# esp-module-cu.net
KiCad netlist of a schematic drawn in EAGLE
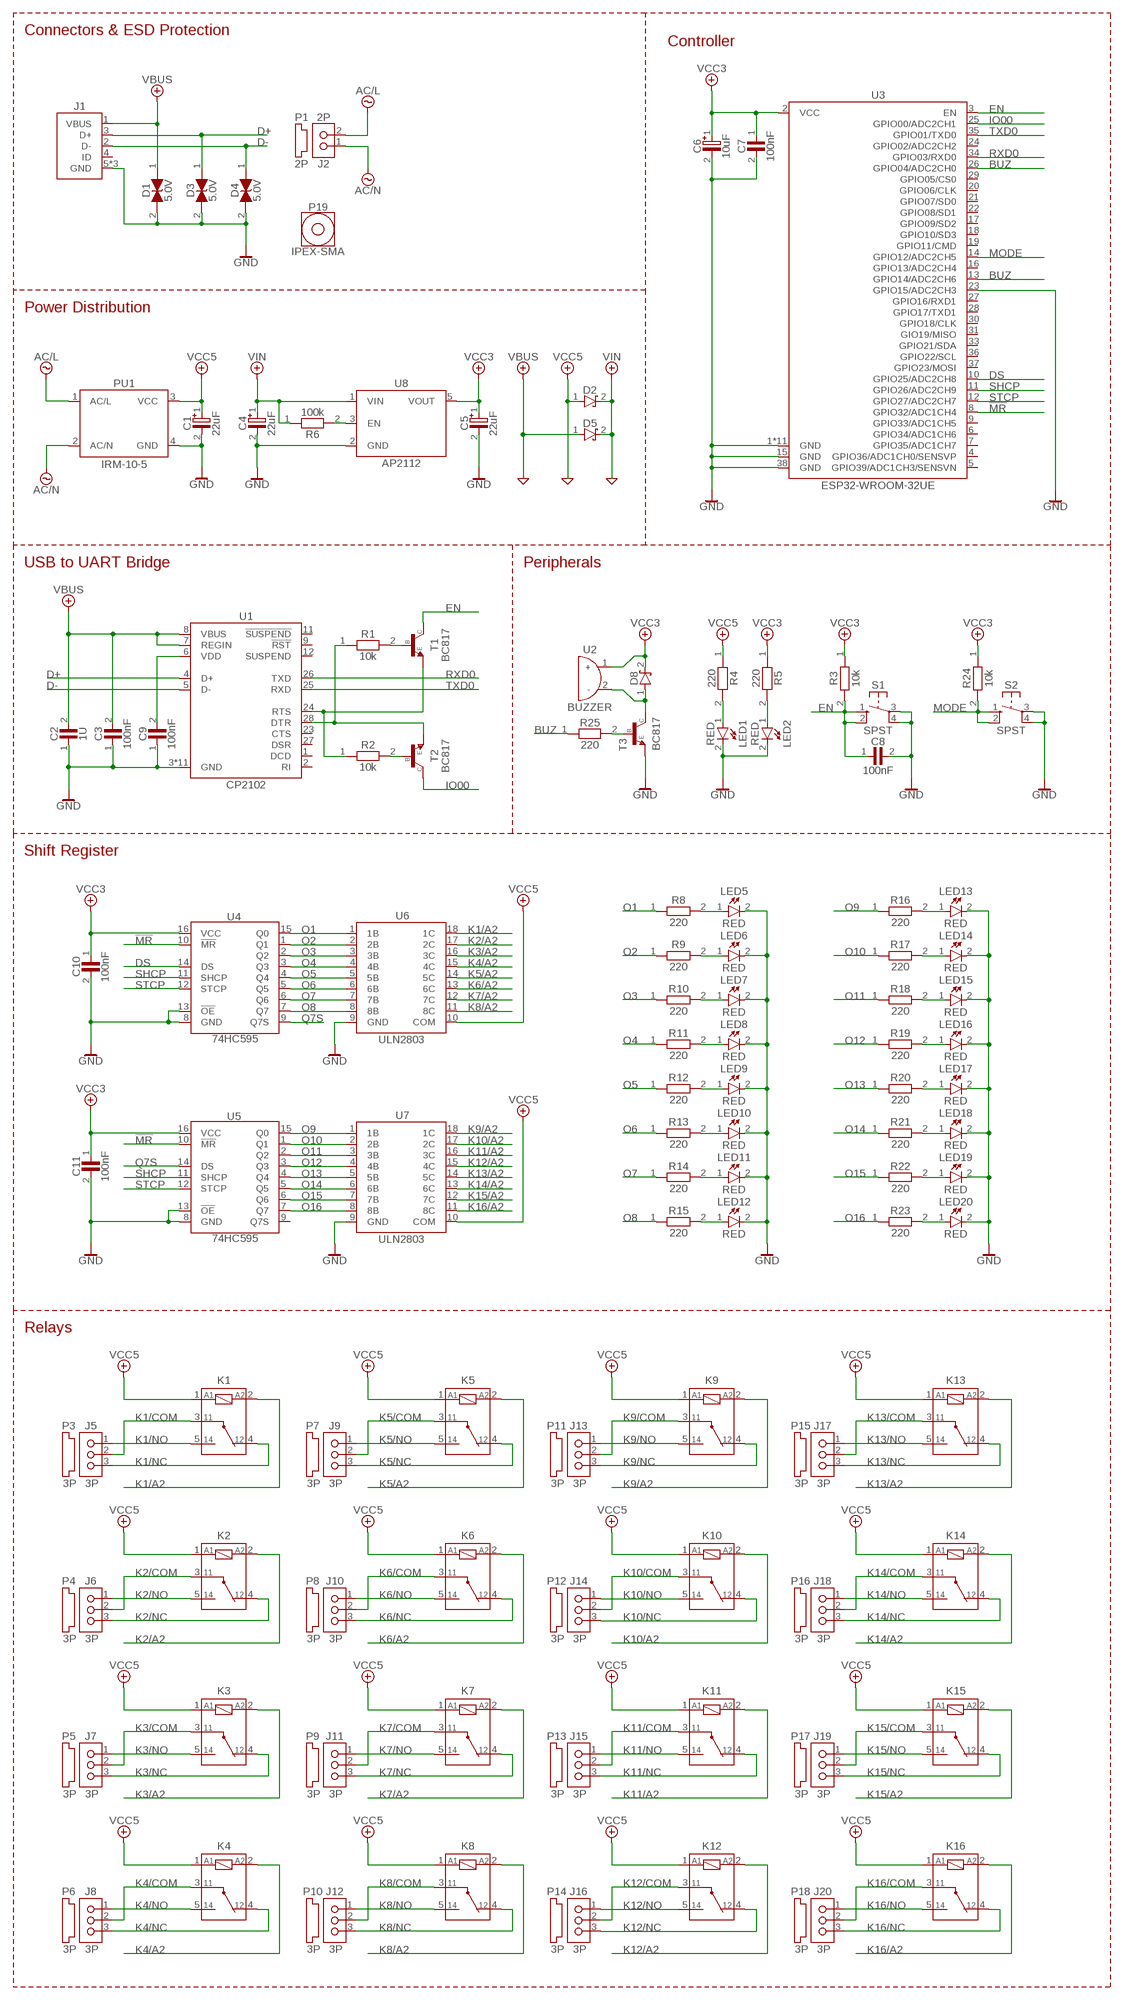
[diagram p0: schematic, sheet 1]

(export (version "E")
  (design (tool "Eeschema 10.0.6"))
  (components
    (comp (ref "C1")
      (value "22uF")
      (footprint "eagle-import:I1206-M3216-D")
      (fields
        (field (name "MF") "Kyocera AVX")
        (field (name "MPN") "TAJA226K010RNJ")
        (field (name "VOLTAGE") "10V")
      )
      (libsource (lib "eagle-import") (part "CAPACITOR-TANTALUM-I1206-M3216-22U"))
    )
    (comp (ref "C2")
      (value "1U")
      (footprint "eagle-import:I0805-M2012-C")
      (fields
        (field (name "MF") " FH (Guangdong Fenghua Advanced Tech)")
        (field (name "MPN") "0805B105K500NT")
        (field (name "TOLERANCE") "10%")
      )
      (libsource (lib "eagle-import") (part "CAPACITOR-CERAMIC-I0805-M2012-1U"))
    )
    (comp (ref "C3")
      (value "100nF")
      (footprint "eagle-import:I0805-M2012-C")
      (fields
        (field (name "MF") "FH (Guangdong Fenghua Advanced Tech)")
        (field (name "MPN") "0805B104K500NT")
        (field (name "TOLERANCE") "10%")
      )
      (libsource (lib "eagle-import") (part "CAPACITOR-CERAMIC-I0805-M2012-100N"))
    )
    (comp (ref "C4")
      (value "22uF")
      (footprint "eagle-import:I1206-M3216-D")
      (fields
        (field (name "MF") "Kyocera AVX")
        (field (name "MPN") "TAJA226K010RNJ")
        (field (name "VOLTAGE") "10V")
      )
      (libsource (lib "eagle-import") (part "CAPACITOR-TANTALUM-I1206-M3216-22U"))
    )
    (comp (ref "C5")
      (value "22uF")
      (footprint "eagle-import:I1206-M3216-D")
      (fields
        (field (name "MF") "Kyocera AVX")
        (field (name "MPN") "TAJA226K010RNJ")
        (field (name "VOLTAGE") "10V")
      )
      (libsource (lib "eagle-import") (part "CAPACITOR-TANTALUM-I1206-M3216-22U"))
    )
    (comp (ref "C6")
      (value "10uF")
      (footprint "eagle-import:I1206-M3216-D")
      (fields
        (field (name "MF") "Kyocera AVX")
        (field (name "MPN") "TAJA106K016RNJ")
        (field (name "VOLTAGE") "16V")
      )
      (libsource (lib "eagle-import") (part "CAPACITOR-TANTALUM-I1206-M3216-10U"))
    )
    (comp (ref "C7")
      (value "100nF")
      (footprint "eagle-import:I0805-M2012-C")
      (fields
        (field (name "MF") "FH (Guangdong Fenghua Advanced Tech)")
        (field (name "MPN") "0805B104K500NT")
        (field (name "TOLERANCE") "10%")
      )
      (libsource (lib "eagle-import") (part "CAPACITOR-CERAMIC-I0805-M2012-100N"))
    )
    (comp (ref "C8")
      (value "100nF")
      (footprint "eagle-import:I0805-M2012-C")
      (fields
        (field (name "MF") "FH (Guangdong Fenghua Advanced Tech)")
        (field (name "MPN") "0805B104K500NT")
        (field (name "TOLERANCE") "10%")
      )
      (libsource (lib "eagle-import") (part "CAPACITOR-CERAMIC-I0805-M2012-100N"))
    )
    (comp (ref "C9")
      (value "100nF")
      (footprint "eagle-import:I0805-M2012-C")
      (fields
        (field (name "MF") "FH (Guangdong Fenghua Advanced Tech)")
        (field (name "MPN") "0805B104K500NT")
        (field (name "TOLERANCE") "10%")
      )
      (libsource (lib "eagle-import") (part "CAPACITOR-CERAMIC-I0805-M2012-100N"))
    )
    (comp (ref "C10")
      (value "100nF")
      (footprint "eagle-import:I0805-M2012-C")
      (fields
        (field (name "MF") "FH (Guangdong Fenghua Advanced Tech)")
        (field (name "MPN") "0805B104K500NT")
        (field (name "TOLERANCE") "10%")
      )
      (libsource (lib "eagle-import") (part "CAPACITOR-CERAMIC-I0805-M2012-100N"))
    )
    (comp (ref "C11")
      (value "100nF")
      (footprint "eagle-import:I0805-M2012-C")
      (fields
        (field (name "MF") "FH (Guangdong Fenghua Advanced Tech)")
        (field (name "MPN") "0805B104K500NT")
        (field (name "TOLERANCE") "10%")
      )
      (libsource (lib "eagle-import") (part "CAPACITOR-CERAMIC-I0805-M2012-100N"))
    )
    (comp (ref "D1")
      (value "5.0V")
      (footprint "eagle-import:SOD-523")
      (fields (field (name "MF") " LRC") (field (name "MPN") "LESD5D5.0CT1G"))
      (libsource (lib "eagle-import") (part "ZENER-BI-SOD-523-5.0V"))
    )
    (comp (ref "D2")
      (value "30V")
      (footprint "eagle-import:SOD-323")
      (fields (field (name "MF") "Diodes Incorporated") (field (name "MPN") "BAT760-7"))
      (libsource (lib "eagle-import") (part "SCHOTTKY-SOD-323-30V"))
    )
    (comp (ref "D3")
      (value "5.0V")
      (footprint "eagle-import:SOD-523")
      (fields (field (name "MF") " LRC") (field (name "MPN") "LESD5D5.0CT1G"))
      (libsource (lib "eagle-import") (part "ZENER-BI-SOD-523-5.0V"))
    )
    (comp (ref "D4")
      (value "5.0V")
      (footprint "eagle-import:SOD-523")
      (fields (field (name "MF") " LRC") (field (name "MPN") "LESD5D5.0CT1G"))
      (libsource (lib "eagle-import") (part "ZENER-BI-SOD-523-5.0V"))
    )
    (comp (ref "D5")
      (value "30V")
      (footprint "eagle-import:SOD-323")
      (fields (field (name "MF") "Diodes Incorporated") (field (name "MPN") "BAT760-7"))
      (libsource (lib "eagle-import") (part "SCHOTTKY-SOD-323-30V"))
    )
    (comp (ref "D8")
      (value "30V")
      (footprint "eagle-import:SOD-323")
      (fields (field (name "MF") "Diodes Incorporated") (field (name "MPN") "BAT760-7"))
      (libsource (lib "eagle-import") (part "SCHOTTKY-SOD-323-30V"))
    )
    (comp (ref "J1")
      (value "USB-A-MICRO-TOP")
      (footprint "eagle-import:USB-A-MICRO-TOP")
      (fields (field (name "MF") "XKB Connectivity") (field (name "MPN") "U255-051N-4BH70-FS"))
      (libsource (lib "eagle-import") (part "USB-A-MICRO-TOP"))
    )
    (comp (ref "J2")
      (value "2P")
      (footprint "eagle-import:KF2EDGV-5.08-2P")
      (fields (field (name "MF") "Cixi Kefa Elec") (field (name "MPN") "KF2EDGV-5.08-2P"))
      (libsource (lib "eagle-import") (part "HEADER-02P-1R-KF2EDGV-5.08-2P"))
    )
    (comp (ref "J5")
      (value "3P")
      (footprint "eagle-import:KF2EDGV-5.08-3P")
      (fields (field (name "MF") " Cixi Kefa Elec") (field (name "MPN") " KF2EDGV-5.08-3P"))
      (libsource (lib "eagle-import") (part "HEADER-03P-1R-KF2EDGV-5.08-3P"))
    )
    (comp (ref "J6")
      (value "3P")
      (footprint "eagle-import:KF2EDGV-5.08-3P")
      (fields (field (name "MF") " Cixi Kefa Elec") (field (name "MPN") " KF2EDGV-5.08-3P"))
      (libsource (lib "eagle-import") (part "HEADER-03P-1R-KF2EDGV-5.08-3P"))
    )
    (comp (ref "J7")
      (value "3P")
      (footprint "eagle-import:KF2EDGV-5.08-3P")
      (fields (field (name "MF") " Cixi Kefa Elec") (field (name "MPN") " KF2EDGV-5.08-3P"))
      (libsource (lib "eagle-import") (part "HEADER-03P-1R-KF2EDGV-5.08-3P"))
    )
    (comp (ref "J8")
      (value "3P")
      (footprint "eagle-import:KF2EDGV-5.08-3P")
      (fields (field (name "MF") " Cixi Kefa Elec") (field (name "MPN") " KF2EDGV-5.08-3P"))
      (libsource (lib "eagle-import") (part "HEADER-03P-1R-KF2EDGV-5.08-3P"))
    )
    (comp (ref "J9")
      (value "3P")
      (footprint "eagle-import:KF2EDGV-5.08-3P")
      (fields (field (name "MF") " Cixi Kefa Elec") (field (name "MPN") " KF2EDGV-5.08-3P"))
      (libsource (lib "eagle-import") (part "HEADER-03P-1R-KF2EDGV-5.08-3P"))
    )
    (comp (ref "J10")
      (value "3P")
      (footprint "eagle-import:KF2EDGV-5.08-3P")
      (fields (field (name "MF") " Cixi Kefa Elec") (field (name "MPN") " KF2EDGV-5.08-3P"))
      (libsource (lib "eagle-import") (part "HEADER-03P-1R-KF2EDGV-5.08-3P"))
    )
    (comp (ref "J11")
      (value "3P")
      (footprint "eagle-import:KF2EDGV-5.08-3P")
      (fields (field (name "MF") " Cixi Kefa Elec") (field (name "MPN") " KF2EDGV-5.08-3P"))
      (libsource (lib "eagle-import") (part "HEADER-03P-1R-KF2EDGV-5.08-3P"))
    )
    (comp (ref "J12")
      (value "3P")
      (footprint "eagle-import:KF2EDGV-5.08-3P")
      (fields (field (name "MF") " Cixi Kefa Elec") (field (name "MPN") " KF2EDGV-5.08-3P"))
      (libsource (lib "eagle-import") (part "HEADER-03P-1R-KF2EDGV-5.08-3P"))
    )
    (comp (ref "J13")
      (value "3P")
      (footprint "eagle-import:KF2EDGV-5.08-3P")
      (fields (field (name "MF") " Cixi Kefa Elec") (field (name "MPN") " KF2EDGV-5.08-3P"))
      (libsource (lib "eagle-import") (part "HEADER-03P-1R-KF2EDGV-5.08-3P"))
    )
    (comp (ref "J14")
      (value "3P")
      (footprint "eagle-import:KF2EDGV-5.08-3P")
      (fields (field (name "MF") " Cixi Kefa Elec") (field (name "MPN") " KF2EDGV-5.08-3P"))
      (libsource (lib "eagle-import") (part "HEADER-03P-1R-KF2EDGV-5.08-3P"))
    )
    (comp (ref "J15")
      (value "3P")
      (footprint "eagle-import:KF2EDGV-5.08-3P")
      (fields (field (name "MF") " Cixi Kefa Elec") (field (name "MPN") " KF2EDGV-5.08-3P"))
      (libsource (lib "eagle-import") (part "HEADER-03P-1R-KF2EDGV-5.08-3P"))
    )
    (comp (ref "J16")
      (value "3P")
      (footprint "eagle-import:KF2EDGV-5.08-3P")
      (fields (field (name "MF") " Cixi Kefa Elec") (field (name "MPN") " KF2EDGV-5.08-3P"))
      (libsource (lib "eagle-import") (part "HEADER-03P-1R-KF2EDGV-5.08-3P"))
    )
    (comp (ref "J17")
      (value "3P")
      (footprint "eagle-import:KF2EDGV-5.08-3P")
      (fields (field (name "MF") " Cixi Kefa Elec") (field (name "MPN") " KF2EDGV-5.08-3P"))
      (libsource (lib "eagle-import") (part "HEADER-03P-1R-KF2EDGV-5.08-3P"))
    )
    (comp (ref "J18")
      (value "3P")
      (footprint "eagle-import:KF2EDGV-5.08-3P")
      (fields (field (name "MF") " Cixi Kefa Elec") (field (name "MPN") " KF2EDGV-5.08-3P"))
      (libsource (lib "eagle-import") (part "HEADER-03P-1R-KF2EDGV-5.08-3P"))
    )
    (comp (ref "J19")
      (value "3P")
      (footprint "eagle-import:KF2EDGV-5.08-3P")
      (fields (field (name "MF") " Cixi Kefa Elec") (field (name "MPN") " KF2EDGV-5.08-3P"))
      (libsource (lib "eagle-import") (part "HEADER-03P-1R-KF2EDGV-5.08-3P"))
    )
    (comp (ref "J20")
      (value "3P")
      (footprint "eagle-import:KF2EDGV-5.08-3P")
      (fields (field (name "MF") " Cixi Kefa Elec") (field (name "MPN") " KF2EDGV-5.08-3P"))
      (libsource (lib "eagle-import") (part "HEADER-03P-1R-KF2EDGV-5.08-3P"))
    )
    (comp (ref "K1")
      (value "5V")
      (footprint "eagle-import:SRD")
      (fields (field (name "MF") "Ningbo Songle Relay") (field (name "MPN") " SRD-05VDC-SL-C"))
      (libsource (lib "eagle-import") (part "RELAY-SPDT-SRD-5V"))
    )
    (comp (ref "K2")
      (value "5V")
      (footprint "eagle-import:SRD")
      (fields (field (name "MF") "Ningbo Songle Relay") (field (name "MPN") " SRD-05VDC-SL-C"))
      (libsource (lib "eagle-import") (part "RELAY-SPDT-SRD-5V"))
    )
    (comp (ref "K3")
      (value "5V")
      (footprint "eagle-import:SRD")
      (fields (field (name "MF") "Ningbo Songle Relay") (field (name "MPN") " SRD-05VDC-SL-C"))
      (libsource (lib "eagle-import") (part "RELAY-SPDT-SRD-5V"))
    )
    (comp (ref "K4")
      (value "5V")
      (footprint "eagle-import:SRD")
      (fields (field (name "MF") "Ningbo Songle Relay") (field (name "MPN") " SRD-05VDC-SL-C"))
      (libsource (lib "eagle-import") (part "RELAY-SPDT-SRD-5V"))
    )
    (comp (ref "K5")
      (value "5V")
      (footprint "eagle-import:SRD")
      (fields (field (name "MF") "Ningbo Songle Relay") (field (name "MPN") " SRD-05VDC-SL-C"))
      (libsource (lib "eagle-import") (part "RELAY-SPDT-SRD-5V"))
    )
    (comp (ref "K6")
      (value "5V")
      (footprint "eagle-import:SRD")
      (fields (field (name "MF") "Ningbo Songle Relay") (field (name "MPN") " SRD-05VDC-SL-C"))
      (libsource (lib "eagle-import") (part "RELAY-SPDT-SRD-5V"))
    )
    (comp (ref "K7")
      (value "5V")
      (footprint "eagle-import:SRD")
      (fields (field (name "MF") "Ningbo Songle Relay") (field (name "MPN") " SRD-05VDC-SL-C"))
      (libsource (lib "eagle-import") (part "RELAY-SPDT-SRD-5V"))
    )
    (comp (ref "K8")
      (value "5V")
      (footprint "eagle-import:SRD")
      (fields (field (name "MF") "Ningbo Songle Relay") (field (name "MPN") " SRD-05VDC-SL-C"))
      (libsource (lib "eagle-import") (part "RELAY-SPDT-SRD-5V"))
    )
    (comp (ref "K9")
      (value "5V")
      (footprint "eagle-import:SRD")
      (fields (field (name "MF") "Ningbo Songle Relay") (field (name "MPN") " SRD-05VDC-SL-C"))
      (libsource (lib "eagle-import") (part "RELAY-SPDT-SRD-5V"))
    )
    (comp (ref "K10")
      (value "5V")
      (footprint "eagle-import:SRD")
      (fields (field (name "MF") "Ningbo Songle Relay") (field (name "MPN") " SRD-05VDC-SL-C"))
      (libsource (lib "eagle-import") (part "RELAY-SPDT-SRD-5V"))
    )
    (comp (ref "K11")
      (value "5V")
      (footprint "eagle-import:SRD")
      (fields (field (name "MF") "Ningbo Songle Relay") (field (name "MPN") " SRD-05VDC-SL-C"))
      (libsource (lib "eagle-import") (part "RELAY-SPDT-SRD-5V"))
    )
    (comp (ref "K12")
      (value "5V")
      (footprint "eagle-import:SRD")
      (fields (field (name "MF") "Ningbo Songle Relay") (field (name "MPN") " SRD-05VDC-SL-C"))
      (libsource (lib "eagle-import") (part "RELAY-SPDT-SRD-5V"))
    )
    (comp (ref "K13")
      (value "5V")
      (footprint "eagle-import:SRD")
      (fields (field (name "MF") "Ningbo Songle Relay") (field (name "MPN") " SRD-05VDC-SL-C"))
      (libsource (lib "eagle-import") (part "RELAY-SPDT-SRD-5V"))
    )
    (comp (ref "K14")
      (value "5V")
      (footprint "eagle-import:SRD")
      (fields (field (name "MF") "Ningbo Songle Relay") (field (name "MPN") " SRD-05VDC-SL-C"))
      (libsource (lib "eagle-import") (part "RELAY-SPDT-SRD-5V"))
    )
    (comp (ref "K15")
      (value "5V")
      (footprint "eagle-import:SRD")
      (fields (field (name "MF") "Ningbo Songle Relay") (field (name "MPN") " SRD-05VDC-SL-C"))
      (libsource (lib "eagle-import") (part "RELAY-SPDT-SRD-5V"))
    )
    (comp (ref "K16")
      (value "5V")
      (footprint "eagle-import:SRD")
      (fields (field (name "MF") "Ningbo Songle Relay") (field (name "MPN") " SRD-05VDC-SL-C"))
      (libsource (lib "eagle-import") (part "RELAY-SPDT-SRD-5V"))
    )
    (comp (ref "LED1")
      (value "RED")
      (footprint "eagle-import:I0805-M2012-D")
      (fields (field (name "MF") "Foshan NationStar Optoelectronics") (field (name "MPN") "FC-2012HRK-620D"))
      (libsource (lib "eagle-import") (part "LED-I0805-M2012-RED"))
    )
    (comp (ref "LED2")
      (value "RED")
      (footprint "eagle-import:I0805-M2012-D")
      (fields (field (name "MF") "Foshan NationStar Optoelectronics") (field (name "MPN") "FC-2012HRK-620D"))
      (libsource (lib "eagle-import") (part "LED-I0805-M2012-RED"))
    )
    (comp (ref "LED5")
      (value "RED")
      (footprint "eagle-import:I0805-M2012-D")
      (fields (field (name "MF") "Foshan NationStar Optoelectronics") (field (name "MPN") "FC-2012HRK-620D"))
      (libsource (lib "eagle-import") (part "LED-I0805-M2012-RED"))
    )
    (comp (ref "LED6")
      (value "RED")
      (footprint "eagle-import:I0805-M2012-D")
      (fields (field (name "MF") "Foshan NationStar Optoelectronics") (field (name "MPN") "FC-2012HRK-620D"))
      (libsource (lib "eagle-import") (part "LED-I0805-M2012-RED"))
    )
    (comp (ref "LED7")
      (value "RED")
      (footprint "eagle-import:I0805-M2012-D")
      (fields (field (name "MF") "Foshan NationStar Optoelectronics") (field (name "MPN") "FC-2012HRK-620D"))
      (libsource (lib "eagle-import") (part "LED-I0805-M2012-RED"))
    )
    (comp (ref "LED8")
      (value "RED")
      (footprint "eagle-import:I0805-M2012-D")
      (fields (field (name "MF") "Foshan NationStar Optoelectronics") (field (name "MPN") "FC-2012HRK-620D"))
      (libsource (lib "eagle-import") (part "LED-I0805-M2012-RED"))
    )
    (comp (ref "LED9")
      (value "RED")
      (footprint "eagle-import:I0805-M2012-D")
      (fields (field (name "MF") "Foshan NationStar Optoelectronics") (field (name "MPN") "FC-2012HRK-620D"))
      (libsource (lib "eagle-import") (part "LED-I0805-M2012-RED"))
    )
    (comp (ref "LED10")
      (value "RED")
      (footprint "eagle-import:I0805-M2012-D")
      (fields (field (name "MF") "Foshan NationStar Optoelectronics") (field (name "MPN") "FC-2012HRK-620D"))
      (libsource (lib "eagle-import") (part "LED-I0805-M2012-RED"))
    )
    (comp (ref "LED11")
      (value "RED")
      (footprint "eagle-import:I0805-M2012-D")
      (fields (field (name "MF") "Foshan NationStar Optoelectronics") (field (name "MPN") "FC-2012HRK-620D"))
      (libsource (lib "eagle-import") (part "LED-I0805-M2012-RED"))
    )
    (comp (ref "LED12")
      (value "RED")
      (footprint "eagle-import:I0805-M2012-D")
      (fields (field (name "MF") "Foshan NationStar Optoelectronics") (field (name "MPN") "FC-2012HRK-620D"))
      (libsource (lib "eagle-import") (part "LED-I0805-M2012-RED"))
    )
    (comp (ref "LED13")
      (value "RED")
      (footprint "eagle-import:I0805-M2012-D")
      (fields (field (name "MF") "Foshan NationStar Optoelectronics") (field (name "MPN") "FC-2012HRK-620D"))
      (libsource (lib "eagle-import") (part "LED-I0805-M2012-RED"))
    )
    (comp (ref "LED14")
      (value "RED")
      (footprint "eagle-import:I0805-M2012-D")
      (fields (field (name "MF") "Foshan NationStar Optoelectronics") (field (name "MPN") "FC-2012HRK-620D"))
      (libsource (lib "eagle-import") (part "LED-I0805-M2012-RED"))
    )
    (comp (ref "LED15")
      (value "RED")
      (footprint "eagle-import:I0805-M2012-D")
      (fields (field (name "MF") "Foshan NationStar Optoelectronics") (field (name "MPN") "FC-2012HRK-620D"))
      (libsource (lib "eagle-import") (part "LED-I0805-M2012-RED"))
    )
    (comp (ref "LED16")
      (value "RED")
      (footprint "eagle-import:I0805-M2012-D")
      (fields (field (name "MF") "Foshan NationStar Optoelectronics") (field (name "MPN") "FC-2012HRK-620D"))
      (libsource (lib "eagle-import") (part "LED-I0805-M2012-RED"))
    )
    (comp (ref "LED17")
      (value "RED")
      (footprint "eagle-import:I0805-M2012-D")
      (fields (field (name "MF") "Foshan NationStar Optoelectronics") (field (name "MPN") "FC-2012HRK-620D"))
      (libsource (lib "eagle-import") (part "LED-I0805-M2012-RED"))
    )
    (comp (ref "LED18")
      (value "RED")
      (footprint "eagle-import:I0805-M2012-D")
      (fields (field (name "MF") "Foshan NationStar Optoelectronics") (field (name "MPN") "FC-2012HRK-620D"))
      (libsource (lib "eagle-import") (part "LED-I0805-M2012-RED"))
    )
    (comp (ref "LED19")
      (value "RED")
      (footprint "eagle-import:I0805-M2012-D")
      (fields (field (name "MF") "Foshan NationStar Optoelectronics") (field (name "MPN") "FC-2012HRK-620D"))
      (libsource (lib "eagle-import") (part "LED-I0805-M2012-RED"))
    )
    (comp (ref "LED20")
      (value "RED")
      (footprint "eagle-import:I0805-M2012-D")
      (fields (field (name "MF") "Foshan NationStar Optoelectronics") (field (name "MPN") "FC-2012HRK-620D"))
      (libsource (lib "eagle-import") (part "LED-I0805-M2012-RED"))
    )
    (comp (ref "P1")
      (value "2P")
      (footprint "eagle-import:CONNECTOR-DEFAULT")
      (fields (field (name "MF") "Cixi Kefa Elec") (field (name "MPN") "KF2EDGK-5.08-2P"))
      (libsource (lib "eagle-import") (part "CONNECTOR-02P-1R-KF2EDGK-5.08"))
    )
    (comp (ref "P3")
      (value "3P")
      (footprint "eagle-import:CONNECTOR-DEFAULT")
      (fields (field (name "MF") "Cixi Kefa Elec") (field (name "MPN") " KF2EDGK-5.08-3P"))
      (libsource (lib "eagle-import") (part "CONNECTOR-03P-1R-KF2EDGK-5.08"))
    )
    (comp (ref "P4")
      (value "3P")
      (footprint "eagle-import:CONNECTOR-DEFAULT")
      (fields (field (name "MF") "Cixi Kefa Elec") (field (name "MPN") " KF2EDGK-5.08-3P"))
      (libsource (lib "eagle-import") (part "CONNECTOR-03P-1R-KF2EDGK-5.08"))
    )
    (comp (ref "P5")
      (value "3P")
      (footprint "eagle-import:CONNECTOR-DEFAULT")
      (fields (field (name "MF") "Cixi Kefa Elec") (field (name "MPN") " KF2EDGK-5.08-3P"))
      (libsource (lib "eagle-import") (part "CONNECTOR-03P-1R-KF2EDGK-5.08"))
    )
    (comp (ref "P6")
      (value "3P")
      (footprint "eagle-import:CONNECTOR-DEFAULT")
      (fields (field (name "MF") "Cixi Kefa Elec") (field (name "MPN") " KF2EDGK-5.08-3P"))
      (libsource (lib "eagle-import") (part "CONNECTOR-03P-1R-KF2EDGK-5.08"))
    )
    (comp (ref "P7")
      (value "3P")
      (footprint "eagle-import:CONNECTOR-DEFAULT")
      (fields (field (name "MF") "Cixi Kefa Elec") (field (name "MPN") " KF2EDGK-5.08-3P"))
      (libsource (lib "eagle-import") (part "CONNECTOR-03P-1R-KF2EDGK-5.08"))
    )
    (comp (ref "P8")
      (value "3P")
      (footprint "eagle-import:CONNECTOR-DEFAULT")
      (fields (field (name "MF") "Cixi Kefa Elec") (field (name "MPN") " KF2EDGK-5.08-3P"))
      (libsource (lib "eagle-import") (part "CONNECTOR-03P-1R-KF2EDGK-5.08"))
    )
    (comp (ref "P9")
      (value "3P")
      (footprint "eagle-import:CONNECTOR-DEFAULT")
      (fields (field (name "MF") "Cixi Kefa Elec") (field (name "MPN") " KF2EDGK-5.08-3P"))
      (libsource (lib "eagle-import") (part "CONNECTOR-03P-1R-KF2EDGK-5.08"))
    )
    (comp (ref "P10")
      (value "3P")
      (footprint "eagle-import:CONNECTOR-DEFAULT")
      (fields (field (name "MF") "Cixi Kefa Elec") (field (name "MPN") " KF2EDGK-5.08-3P"))
      (libsource (lib "eagle-import") (part "CONNECTOR-03P-1R-KF2EDGK-5.08"))
    )
    (comp (ref "P11")
      (value "3P")
      (footprint "eagle-import:CONNECTOR-DEFAULT")
      (fields (field (name "MF") "Cixi Kefa Elec") (field (name "MPN") " KF2EDGK-5.08-3P"))
      (libsource (lib "eagle-import") (part "CONNECTOR-03P-1R-KF2EDGK-5.08"))
    )
    (comp (ref "P12")
      (value "3P")
      (footprint "eagle-import:CONNECTOR-DEFAULT")
      (fields (field (name "MF") "Cixi Kefa Elec") (field (name "MPN") " KF2EDGK-5.08-3P"))
      (libsource (lib "eagle-import") (part "CONNECTOR-03P-1R-KF2EDGK-5.08"))
    )
    (comp (ref "P13")
      (value "3P")
      (footprint "eagle-import:CONNECTOR-DEFAULT")
      (fields (field (name "MF") "Cixi Kefa Elec") (field (name "MPN") " KF2EDGK-5.08-3P"))
      (libsource (lib "eagle-import") (part "CONNECTOR-03P-1R-KF2EDGK-5.08"))
    )
    (comp (ref "P14")
      (value "3P")
      (footprint "eagle-import:CONNECTOR-DEFAULT")
      (fields (field (name "MF") "Cixi Kefa Elec") (field (name "MPN") " KF2EDGK-5.08-3P"))
      (libsource (lib "eagle-import") (part "CONNECTOR-03P-1R-KF2EDGK-5.08"))
    )
    (comp (ref "P15")
      (value "3P")
      (footprint "eagle-import:CONNECTOR-DEFAULT")
      (fields (field (name "MF") "Cixi Kefa Elec") (field (name "MPN") " KF2EDGK-5.08-3P"))
      (libsource (lib "eagle-import") (part "CONNECTOR-03P-1R-KF2EDGK-5.08"))
    )
    (comp (ref "P16")
      (value "3P")
      (footprint "eagle-import:CONNECTOR-DEFAULT")
      (fields (field (name "MF") "Cixi Kefa Elec") (field (name "MPN") " KF2EDGK-5.08-3P"))
      (libsource (lib "eagle-import") (part "CONNECTOR-03P-1R-KF2EDGK-5.08"))
    )
    (comp (ref "P17")
      (value "3P")
      (footprint "eagle-import:CONNECTOR-DEFAULT")
      (fields (field (name "MF") "Cixi Kefa Elec") (field (name "MPN") " KF2EDGK-5.08-3P"))
      (libsource (lib "eagle-import") (part "CONNECTOR-03P-1R-KF2EDGK-5.08"))
    )
    (comp (ref "P18")
      (value "3P")
      (footprint "eagle-import:CONNECTOR-DEFAULT")
      (fields (field (name "MF") "Cixi Kefa Elec") (field (name "MPN") " KF2EDGK-5.08-3P"))
      (libsource (lib "eagle-import") (part "CONNECTOR-03P-1R-KF2EDGK-5.08"))
    )
    (comp (ref "P19")
      (value "IPEX-SMA")
      (footprint "eagle-import:SMA")
      (fields (field (name "MF") "HJ-IPEX1-SMA-RG1.13-35mm") (field (name "MPN") "HJ Tech"))
      (libsource (lib "eagle-import") (part "IPEX-SMA"))
    )
    (comp (ref "PU1")
      (value "IRM-10-5")
      (footprint "eagle-import:IRM-10")
      (fields (field (name "MF") "Mean Well"))
      (libsource (lib "eagle-import") (part "POWER-SUPPLY-IRM-10-5V"))
    )
    (comp (ref "R1")
      (value "10k")
      (footprint "eagle-import:I0805-M2012-R")
      (fields (field (name "MF") " UNI-ROYAL(Uniroyal Elec)") (field (name "MPN") "0805W8F1002T5E"))
      (libsource (lib "eagle-import") (part "RESISTOR-I0805-M2012-10K"))
    )
    (comp (ref "R2")
      (value "10k")
      (footprint "eagle-import:I0805-M2012-R")
      (fields (field (name "MF") " UNI-ROYAL(Uniroyal Elec)") (field (name "MPN") "0805W8F1002T5E"))
      (libsource (lib "eagle-import") (part "RESISTOR-I0805-M2012-10K"))
    )
    (comp (ref "R3")
      (value "10k")
      (footprint "eagle-import:I0805-M2012-R")
      (fields (field (name "MF") " UNI-ROYAL(Uniroyal Elec)") (field (name "MPN") "0805W8F1002T5E"))
      (libsource (lib "eagle-import") (part "RESISTOR-I0805-M2012-10K"))
    )
    (comp (ref "R4")
      (value "220")
      (footprint "eagle-import:I0805-M2012-R")
      (fields (field (name "MF") "UNI-ROYAL(Uniroyal Elec)") (field (name "MPN") "0805W8F2200T5E"))
      (libsource (lib "eagle-import") (part "RESISTOR-I0805-M2012-220"))
    )
    (comp (ref "R5")
      (value "220")
      (footprint "eagle-import:I0805-M2012-R")
      (fields (field (name "MF") "UNI-ROYAL(Uniroyal Elec)") (field (name "MPN") "0805W8F2200T5E"))
      (libsource (lib "eagle-import") (part "RESISTOR-I0805-M2012-220"))
    )
    (comp (ref "R6")
      (value "100k")
      (footprint "eagle-import:I0805-M2012-R")
      (fields (field (name "MF") "UNI-ROYAL(Uniroyal Elec)") (field (name "MPN") "0805W8F1003T5E"))
      (libsource (lib "eagle-import") (part "RESISTOR-I0805-M2012-100K"))
    )
    (comp (ref "R8")
      (value "220")
      (footprint "eagle-import:I0805-M2012-R")
      (fields (field (name "MF") "UNI-ROYAL(Uniroyal Elec)") (field (name "MPN") "0805W8F2200T5E"))
      (libsource (lib "eagle-import") (part "RESISTOR-I0805-M2012-220"))
    )
    (comp (ref "R9")
      (value "220")
      (footprint "eagle-import:I0805-M2012-R")
      (fields (field (name "MF") "UNI-ROYAL(Uniroyal Elec)") (field (name "MPN") "0805W8F2200T5E"))
      (libsource (lib "eagle-import") (part "RESISTOR-I0805-M2012-220"))
    )
    (comp (ref "R10")
      (value "220")
      (footprint "eagle-import:I0805-M2012-R")
      (fields (field (name "MF") "UNI-ROYAL(Uniroyal Elec)") (field (name "MPN") "0805W8F2200T5E"))
      (libsource (lib "eagle-import") (part "RESISTOR-I0805-M2012-220"))
    )
    (comp (ref "R11")
      (value "220")
      (footprint "eagle-import:I0805-M2012-R")
      (fields (field (name "MF") "UNI-ROYAL(Uniroyal Elec)") (field (name "MPN") "0805W8F2200T5E"))
      (libsource (lib "eagle-import") (part "RESISTOR-I0805-M2012-220"))
    )
    (comp (ref "R12")
      (value "220")
      (footprint "eagle-import:I0805-M2012-R")
      (fields (field (name "MF") "UNI-ROYAL(Uniroyal Elec)") (field (name "MPN") "0805W8F2200T5E"))
      (libsource (lib "eagle-import") (part "RESISTOR-I0805-M2012-220"))
    )
    (comp (ref "R13")
      (value "220")
      (footprint "eagle-import:I0805-M2012-R")
      (fields (field (name "MF") "UNI-ROYAL(Uniroyal Elec)") (field (name "MPN") "0805W8F2200T5E"))
      (libsource (lib "eagle-import") (part "RESISTOR-I0805-M2012-220"))
    )
    (comp (ref "R14")
      (value "220")
      (footprint "eagle-import:I0805-M2012-R")
      (fields (field (name "MF") "UNI-ROYAL(Uniroyal Elec)") (field (name "MPN") "0805W8F2200T5E"))
      (libsource (lib "eagle-import") (part "RESISTOR-I0805-M2012-220"))
    )
    (comp (ref "R15")
      (value "220")
      (footprint "eagle-import:I0805-M2012-R")
      (fields (field (name "MF") "UNI-ROYAL(Uniroyal Elec)") (field (name "MPN") "0805W8F2200T5E"))
      (libsource (lib "eagle-import") (part "RESISTOR-I0805-M2012-220"))
    )
    (comp (ref "R16")
      (value "220")
      (footprint "eagle-import:I0805-M2012-R")
      (fields (field (name "MF") "UNI-ROYAL(Uniroyal Elec)") (field (name "MPN") "0805W8F2200T5E"))
      (libsource (lib "eagle-import") (part "RESISTOR-I0805-M2012-220"))
    )
    (comp (ref "R17")
      (value "220")
      (footprint "eagle-import:I0805-M2012-R")
      (fields (field (name "MF") "UNI-ROYAL(Uniroyal Elec)") (field (name "MPN") "0805W8F2200T5E"))
      (libsource (lib "eagle-import") (part "RESISTOR-I0805-M2012-220"))
    )
    (comp (ref "R18")
      (value "220")
      (footprint "eagle-import:I0805-M2012-R")
      (fields (field (name "MF") "UNI-ROYAL(Uniroyal Elec)") (field (name "MPN") "0805W8F2200T5E"))
      (libsource (lib "eagle-import") (part "RESISTOR-I0805-M2012-220"))
    )
    (comp (ref "R19")
      (value "220")
      (footprint "eagle-import:I0805-M2012-R")
      (fields (field (name "MF") "UNI-ROYAL(Uniroyal Elec)") (field (name "MPN") "0805W8F2200T5E"))
      (libsource (lib "eagle-import") (part "RESISTOR-I0805-M2012-220"))
    )
    (comp (ref "R20")
      (value "220")
      (footprint "eagle-import:I0805-M2012-R")
      (fields (field (name "MF") "UNI-ROYAL(Uniroyal Elec)") (field (name "MPN") "0805W8F2200T5E"))
      (libsource (lib "eagle-import") (part "RESISTOR-I0805-M2012-220"))
    )
    (comp (ref "R21")
      (value "220")
      (footprint "eagle-import:I0805-M2012-R")
      (fields (field (name "MF") "UNI-ROYAL(Uniroyal Elec)") (field (name "MPN") "0805W8F2200T5E"))
      (libsource (lib "eagle-import") (part "RESISTOR-I0805-M2012-220"))
    )
    (comp (ref "R22")
      (value "220")
      (footprint "eagle-import:I0805-M2012-R")
      (fields (field (name "MF") "UNI-ROYAL(Uniroyal Elec)") (field (name "MPN") "0805W8F2200T5E"))
      (libsource (lib "eagle-import") (part "RESISTOR-I0805-M2012-220"))
    )
    (comp (ref "R23")
      (value "220")
      (footprint "eagle-import:I0805-M2012-R")
      (fields (field (name "MF") "UNI-ROYAL(Uniroyal Elec)") (field (name "MPN") "0805W8F2200T5E"))
      (libsource (lib "eagle-import") (part "RESISTOR-I0805-M2012-220"))
    )
    (comp (ref "R24")
      (value "10k")
      (footprint "eagle-import:I0805-M2012-R")
      (fields (field (name "MF") " UNI-ROYAL(Uniroyal Elec)") (field (name "MPN") "0805W8F1002T5E"))
      (libsource (lib "eagle-import") (part "RESISTOR-I0805-M2012-10K"))
    )
    (comp (ref "R25")
      (value "220")
      (footprint "eagle-import:I0805-M2012-R")
      (fields (field (name "MF") "UNI-ROYAL(Uniroyal Elec)") (field (name "MPN") "0805W8F2200T5E"))
      (libsource (lib "eagle-import") (part "RESISTOR-I0805-M2012-220"))
    )
    (comp (ref "S1")
      (value "SPST")
      (footprint "eagle-import:SMD-SW-4")
      (fields
        (field (name "MF") "XKB Enterprise")
        (field (name "MPN") "TS-1187A-B-A-B")
        (field (name "VOLTAGE") "12V")
      )
      (libsource (lib "eagle-import") (part "SWITCH-12V-50MA"))
    )
    (comp (ref "S2")
      (value "SPST")
      (footprint "eagle-import:SMD-SW-4")
      (fields
        (field (name "MF") "XKB Enterprise")
        (field (name "MPN") "TS-1187A-B-A-B")
        (field (name "VOLTAGE") "12V")
      )
      (libsource (lib "eagle-import") (part "SWITCH-12V-50MA"))
    )
    (comp (ref "T1")
      (value "BC817")
      (footprint "eagle-import:SOT-23-3")
      (fields (field (name "MF") " Nexperia") (field (name "MPN") " BC817-40,215"))
      (libsource (lib "eagle-import") (part "TRANSISTOR-NPN-SOT-23-3"))
    )
    (comp (ref "T2")
      (value "BC817")
      (footprint "eagle-import:SOT-23-3")
      (fields (field (name "MF") " Nexperia") (field (name "MPN") " BC817-40,215"))
      (libsource (lib "eagle-import") (part "TRANSISTOR-NPN-SOT-23-3"))
    )
    (comp (ref "T3")
      (value "BC817")
      (footprint "eagle-import:SOT-23-3")
      (fields (field (name "MF") " Nexperia") (field (name "MPN") " BC817-40,215"))
      (libsource (lib "eagle-import") (part "TRANSISTOR-NPN-SOT-23-3"))
    )
    (comp (ref "U1")
      (value "CP2102")
      (footprint "eagle-import:QFN-28")
      (fields (field (name "MF") "SILICON LABS") (field (name "MPN") "CP2102-GMR"))
      (libsource (lib "eagle-import") (part "CP2102-QFN-28"))
    )
    (comp (ref "U2")
      (value "BUZZER")
      (footprint "eagle-import:SMD-BUZZER")
      (fields (field (name "MF") "MLT-7525") (field (name "MPN") "Jiangsu Huaneng Elec"))
      (libsource (lib "eagle-import") (part "BUZZER"))
    )
    (comp (ref "U3")
      (value "ESP32-WROOM-32UE")
      (footprint "eagle-import:ESP32-WROOM-32UE")
      (fields (field (name "MF") "Espressif Systems") (field (name "MPN") "ESP32-WROOM-32UE-N16"))
      (libsource (lib "eagle-import") (part "ESP32-WROOM-32UE"))
    )
    (comp (ref "U4")
      (value "74HC595")
      (footprint "eagle-import:SOIC-16")
      (fields (field (name "MF") "74HC595D,118") (field (name "MPN") "Nexperia"))
      (libsource (lib "eagle-import") (part "74HC595-SOIC-16"))
    )
    (comp (ref "U5")
      (value "74HC595")
      (footprint "eagle-import:SOIC-16")
      (fields (field (name "MF") "74HC595D,118") (field (name "MPN") "Nexperia"))
      (libsource (lib "eagle-import") (part "74HC595-SOIC-16"))
    )
    (comp (ref "U6")
      (value "ULN2803")
      (footprint "eagle-import:SOIC-18")
      (fields (field (name "MF") "Texas Instruments"))
      (libsource (lib "eagle-import") (part "ULN2803A-SOIC-18"))
    )
    (comp (ref "U7")
      (value "ULN2803")
      (footprint "eagle-import:SOIC-18")
      (fields (field (name "MF") "Texas Instruments"))
      (libsource (lib "eagle-import") (part "ULN2803A-SOIC-18"))
    )
    (comp (ref "U8")
      (value "AP2112")
      (footprint "eagle-import:SOT-25-5")
      (fields (field (name "MF") "TECH PUBLIC") (field (name "MPN") "TPAP2112K-3.3TRG1"))
      (libsource (lib "eagle-import") (part "AP2112-SOT-25-5"))
    )
  )
  (nets
    (net (code "1") (name "/BUZ") (class "Default")
      (node (ref "R25") (pin "1") (pinfunction "1_1") (pintype "passive"))
      (node (ref "U3") (pin "13") (pinfunction "GPIO14/ADC2CH6_13") (pintype "bidirectional"))
      (node (ref "U3") (pin "26") (pinfunction "GPIO04/ADC2CH0_26") (pintype "bidirectional"))
    )
    (net (code "2") (name "/D+") (class "Default")
      (node (ref "D3") (pin "1") (pinfunction "A_1") (pintype "passive"))
      (node (ref "J1") (pin "3") (pinfunction "D+_3") (pintype "bidirectional"))
      (node (ref "U1") (pin "4") (pinfunction "D+_4") (pintype "bidirectional"))
    )
    (net (code "3") (name "/D-") (class "Default")
      (node (ref "D4") (pin "1") (pinfunction "A_1") (pintype "passive"))
      (node (ref "J1") (pin "2") (pinfunction "D-_2") (pintype "bidirectional"))
      (node (ref "U1") (pin "5") (pinfunction "D-_5") (pintype "bidirectional"))
    )
    (net (code "4") (name "/DS") (class "Default")
      (node (ref "U3") (pin "10") (pinfunction "GPIO25/ADC2CH8_10") (pintype "bidirectional"))
      (node (ref "U4") (pin "14") (pinfunction "DS_14") (pintype "bidirectional"))
    )
    (net (code "5") (name "/EN") (class "Default")
      (node (ref "C8") (pin "1") (pinfunction "1_1") (pintype "passive"))
      (node (ref "R3") (pin "2") (pinfunction "2_2") (pintype "passive"))
      (node (ref "S1") (pin "1") (pinfunction "1_1") (pintype "bidirectional"))
      (node (ref "S1") (pin "2") (pinfunction "2_2") (pintype "bidirectional"))
      (node (ref "T1") (pin "3") (pinfunction "C_3") (pintype "passive"))
      (node (ref "U3") (pin "3") (pinfunction "EN_3") (pintype "bidirectional"))
    )
    (net (code "6") (name "/IO00") (class "Default")
      (node (ref "T2") (pin "3") (pinfunction "C_3") (pintype "passive"))
      (node (ref "U3") (pin "25") (pinfunction "GPIO00/ADC2CH1_25") (pintype "bidirectional"))
    )
    (net (code "7") (name "/K1{slash}A2") (class "Default")
      (node (ref "K1") (pin "2") (pinfunction "A2_2") (pintype "passive"))
      (node (ref "U6") (pin "18") (pinfunction "1C_18") (pintype "bidirectional"))
    )
    (net (code "8") (name "/K1{slash}COM") (class "Default")
      (node (ref "J5") (pin "2") (pinfunction "02_2") (pintype "passive"))
      (node (ref "K1") (pin "3") (pinfunction "11_3") (pintype "passive"))
    )
    (net (code "9") (name "/K1{slash}NC") (class "Default")
      (node (ref "J5") (pin "3") (pinfunction "03_3") (pintype "passive"))
      (node (ref "K1") (pin "4") (pinfunction "12_4") (pintype "passive"))
    )
    (net (code "10") (name "/K1{slash}NO") (class "Default")
      (node (ref "J5") (pin "1") (pinfunction "01_1") (pintype "passive"))
      (node (ref "K1") (pin "5") (pinfunction "14_5") (pintype "passive"))
    )
    (net (code "11") (name "/K2{slash}A2") (class "Default")
      (node (ref "K2") (pin "2") (pinfunction "A2_2") (pintype "passive"))
      (node (ref "U6") (pin "17") (pinfunction "2C_17") (pintype "bidirectional"))
    )
    (net (code "12") (name "/K2{slash}COM") (class "Default")
      (node (ref "J6") (pin "2") (pinfunction "02_2") (pintype "passive"))
      (node (ref "K2") (pin "3") (pinfunction "11_3") (pintype "passive"))
    )
    (net (code "13") (name "/K2{slash}NC") (class "Default")
      (node (ref "J6") (pin "3") (pinfunction "03_3") (pintype "passive"))
      (node (ref "K2") (pin "4") (pinfunction "12_4") (pintype "passive"))
    )
    (net (code "14") (name "/K2{slash}NO") (class "Default")
      (node (ref "J6") (pin "1") (pinfunction "01_1") (pintype "passive"))
      (node (ref "K2") (pin "5") (pinfunction "14_5") (pintype "passive"))
    )
    (net (code "15") (name "/K3{slash}A2") (class "Default")
      (node (ref "K3") (pin "2") (pinfunction "A2_2") (pintype "passive"))
      (node (ref "U6") (pin "16") (pinfunction "3C_16") (pintype "bidirectional"))
    )
    (net (code "16") (name "/K3{slash}COM") (class "Default")
      (node (ref "J7") (pin "2") (pinfunction "02_2") (pintype "passive"))
      (node (ref "K3") (pin "3") (pinfunction "11_3") (pintype "passive"))
    )
    (net (code "17") (name "/K3{slash}NC") (class "Default")
      (node (ref "J7") (pin "3") (pinfunction "03_3") (pintype "passive"))
      (node (ref "K3") (pin "4") (pinfunction "12_4") (pintype "passive"))
    )
    (net (code "18") (name "/K3{slash}NO") (class "Default")
      (node (ref "J7") (pin "1") (pinfunction "01_1") (pintype "passive"))
      (node (ref "K3") (pin "5") (pinfunction "14_5") (pintype "passive"))
    )
    (net (code "19") (name "/K4{slash}A2") (class "Default")
      (node (ref "K4") (pin "2") (pinfunction "A2_2") (pintype "passive"))
      (node (ref "U6") (pin "15") (pinfunction "4C_15") (pintype "bidirectional"))
    )
    (net (code "20") (name "/K4{slash}COM") (class "Default")
      (node (ref "J8") (pin "2") (pinfunction "02_2") (pintype "passive"))
      (node (ref "K4") (pin "3") (pinfunction "11_3") (pintype "passive"))
    )
    (net (code "21") (name "/K4{slash}NC") (class "Default")
      (node (ref "J8") (pin "3") (pinfunction "03_3") (pintype "passive"))
      (node (ref "K4") (pin "4") (pinfunction "12_4") (pintype "passive"))
    )
    (net (code "22") (name "/K4{slash}NO") (class "Default")
      (node (ref "J8") (pin "1") (pinfunction "01_1") (pintype "passive"))
      (node (ref "K4") (pin "5") (pinfunction "14_5") (pintype "passive"))
    )
    (net (code "23") (name "/K5{slash}A2") (class "Default")
      (node (ref "K5") (pin "2") (pinfunction "A2_2") (pintype "passive"))
      (node (ref "U6") (pin "14") (pinfunction "5C_14") (pintype "bidirectional"))
    )
    (net (code "24") (name "/K5{slash}COM") (class "Default")
      (node (ref "J9") (pin "2") (pinfunction "02_2") (pintype "passive"))
      (node (ref "K5") (pin "3") (pinfunction "11_3") (pintype "passive"))
    )
    (net (code "25") (name "/K5{slash}NC") (class "Default")
      (node (ref "J9") (pin "3") (pinfunction "03_3") (pintype "passive"))
      (node (ref "K5") (pin "4") (pinfunction "12_4") (pintype "passive"))
    )
    (net (code "26") (name "/K5{slash}NO") (class "Default")
      (node (ref "J9") (pin "1") (pinfunction "01_1") (pintype "passive"))
      (node (ref "K5") (pin "5") (pinfunction "14_5") (pintype "passive"))
    )
    (net (code "27") (name "/K6{slash}A2") (class "Default")
      (node (ref "K6") (pin "2") (pinfunction "A2_2") (pintype "passive"))
      (node (ref "U6") (pin "13") (pinfunction "6C_13") (pintype "bidirectional"))
    )
    (net (code "28") (name "/K6{slash}COM") (class "Default")
      (node (ref "J10") (pin "2") (pinfunction "02_2") (pintype "passive"))
      (node (ref "K6") (pin "3") (pinfunction "11_3") (pintype "passive"))
    )
    (net (code "29") (name "/K6{slash}NC") (class "Default")
      (node (ref "J10") (pin "3") (pinfunction "03_3") (pintype "passive"))
      (node (ref "K6") (pin "4") (pinfunction "12_4") (pintype "passive"))
    )
    (net (code "30") (name "/K6{slash}NO") (class "Default")
      (node (ref "J10") (pin "1") (pinfunction "01_1") (pintype "passive"))
      (node (ref "K6") (pin "5") (pinfunction "14_5") (pintype "passive"))
    )
    (net (code "31") (name "/K7{slash}A2") (class "Default")
      (node (ref "K7") (pin "2") (pinfunction "A2_2") (pintype "passive"))
      (node (ref "U6") (pin "12") (pinfunction "7C_12") (pintype "bidirectional"))
    )
    (net (code "32") (name "/K7{slash}COM") (class "Default")
      (node (ref "J11") (pin "2") (pinfunction "02_2") (pintype "passive"))
      (node (ref "K7") (pin "3") (pinfunction "11_3") (pintype "passive"))
    )
    (net (code "33") (name "/K7{slash}NC") (class "Default")
      (node (ref "J11") (pin "3") (pinfunction "03_3") (pintype "passive"))
      (node (ref "K7") (pin "4") (pinfunction "12_4") (pintype "passive"))
    )
    (net (code "34") (name "/K7{slash}NO") (class "Default")
      (node (ref "J11") (pin "1") (pinfunction "01_1") (pintype "passive"))
      (node (ref "K7") (pin "5") (pinfunction "14_5") (pintype "passive"))
    )
    (net (code "35") (name "/K8{slash}A2") (class "Default")
      (node (ref "K8") (pin "2") (pinfunction "A2_2") (pintype "passive"))
      (node (ref "U6") (pin "11") (pinfunction "8C_11") (pintype "bidirectional"))
    )
    (net (code "36") (name "/K8{slash}COM") (class "Default")
      (node (ref "J12") (pin "2") (pinfunction "02_2") (pintype "passive"))
      (node (ref "K8") (pin "3") (pinfunction "11_3") (pintype "passive"))
    )
    (net (code "37") (name "/K8{slash}NC") (class "Default")
      (node (ref "J12") (pin "3") (pinfunction "03_3") (pintype "passive"))
      (node (ref "K8") (pin "4") (pinfunction "12_4") (pintype "passive"))
    )
    (net (code "38") (name "/K8{slash}NO") (class "Default")
      (node (ref "J12") (pin "1") (pinfunction "01_1") (pintype "passive"))
      (node (ref "K8") (pin "5") (pinfunction "14_5") (pintype "passive"))
    )
    (net (code "39") (name "/K9{slash}A2") (class "Default")
      (node (ref "K9") (pin "2") (pinfunction "A2_2") (pintype "passive"))
      (node (ref "U7") (pin "18") (pinfunction "1C_18") (pintype "bidirectional"))
    )
    (net (code "40") (name "/K9{slash}COM") (class "Default")
      (node (ref "J13") (pin "2") (pinfunction "02_2") (pintype "passive"))
      (node (ref "K9") (pin "3") (pinfunction "11_3") (pintype "passive"))
    )
    (net (code "41") (name "/K9{slash}NC") (class "Default")
      (node (ref "J13") (pin "3") (pinfunction "03_3") (pintype "passive"))
      (node (ref "K9") (pin "4") (pinfunction "12_4") (pintype "passive"))
    )
    (net (code "42") (name "/K9{slash}NO") (class "Default")
      (node (ref "J13") (pin "1") (pinfunction "01_1") (pintype "passive"))
      (node (ref "K9") (pin "5") (pinfunction "14_5") (pintype "passive"))
    )
    (net (code "43") (name "/K10{slash}A2") (class "Default")
      (node (ref "K10") (pin "2") (pinfunction "A2_2") (pintype "passive"))
      (node (ref "U7") (pin "17") (pinfunction "2C_17") (pintype "bidirectional"))
    )
    (net (code "44") (name "/K10{slash}COM") (class "Default")
      (node (ref "J14") (pin "2") (pinfunction "02_2") (pintype "passive"))
      (node (ref "K10") (pin "3") (pinfunction "11_3") (pintype "passive"))
    )
    (net (code "45") (name "/K10{slash}NC") (class "Default")
      (node (ref "J14") (pin "3") (pinfunction "03_3") (pintype "passive"))
      (node (ref "K10") (pin "4") (pinfunction "12_4") (pintype "passive"))
    )
    (net (code "46") (name "/K10{slash}NO") (class "Default")
      (node (ref "J14") (pin "1") (pinfunction "01_1") (pintype "passive"))
      (node (ref "K10") (pin "5") (pinfunction "14_5") (pintype "passive"))
    )
    (net (code "47") (name "/K11{slash}A2") (class "Default")
      (node (ref "K11") (pin "2") (pinfunction "A2_2") (pintype "passive"))
      (node (ref "U7") (pin "16") (pinfunction "3C_16") (pintype "bidirectional"))
    )
    (net (code "48") (name "/K11{slash}COM") (class "Default")
      (node (ref "J15") (pin "2") (pinfunction "02_2") (pintype "passive"))
      (node (ref "K11") (pin "3") (pinfunction "11_3") (pintype "passive"))
    )
    (net (code "49") (name "/K11{slash}NC") (class "Default")
      (node (ref "J15") (pin "3") (pinfunction "03_3") (pintype "passive"))
      (node (ref "K11") (pin "4") (pinfunction "12_4") (pintype "passive"))
    )
    (net (code "50") (name "/K11{slash}NO") (class "Default")
      (node (ref "J15") (pin "1") (pinfunction "01_1") (pintype "passive"))
      (node (ref "K11") (pin "5") (pinfunction "14_5") (pintype "passive"))
    )
    (net (code "51") (name "/K12{slash}A2") (class "Default")
      (node (ref "K12") (pin "2") (pinfunction "A2_2") (pintype "passive"))
      (node (ref "U7") (pin "15") (pinfunction "4C_15") (pintype "bidirectional"))
    )
    (net (code "52") (name "/K12{slash}COM") (class "Default")
      (node (ref "J16") (pin "2") (pinfunction "02_2") (pintype "passive"))
      (node (ref "K12") (pin "3") (pinfunction "11_3") (pintype "passive"))
    )
    (net (code "53") (name "/K12{slash}NC") (class "Default")
      (node (ref "J16") (pin "3") (pinfunction "03_3") (pintype "passive"))
      (node (ref "K12") (pin "4") (pinfunction "12_4") (pintype "passive"))
    )
    (net (code "54") (name "/K12{slash}NO") (class "Default")
      (node (ref "J16") (pin "1") (pinfunction "01_1") (pintype "passive"))
      (node (ref "K12") (pin "5") (pinfunction "14_5") (pintype "passive"))
    )
    (net (code "55") (name "/K13{slash}A2") (class "Default")
      (node (ref "K13") (pin "2") (pinfunction "A2_2") (pintype "passive"))
      (node (ref "U7") (pin "14") (pinfunction "5C_14") (pintype "bidirectional"))
    )
    (net (code "56") (name "/K13{slash}COM") (class "Default")
      (node (ref "J17") (pin "2") (pinfunction "02_2") (pintype "passive"))
      (node (ref "K13") (pin "3") (pinfunction "11_3") (pintype "passive"))
    )
    (net (code "57") (name "/K13{slash}NC") (class "Default")
      (node (ref "J17") (pin "3") (pinfunction "03_3") (pintype "passive"))
      (node (ref "K13") (pin "4") (pinfunction "12_4") (pintype "passive"))
    )
    (net (code "58") (name "/K13{slash}NO") (class "Default")
      (node (ref "J17") (pin "1") (pinfunction "01_1") (pintype "passive"))
      (node (ref "K13") (pin "5") (pinfunction "14_5") (pintype "passive"))
    )
    (net (code "59") (name "/K14{slash}A2") (class "Default")
      (node (ref "K14") (pin "2") (pinfunction "A2_2") (pintype "passive"))
      (node (ref "U7") (pin "13") (pinfunction "6C_13") (pintype "bidirectional"))
    )
    (net (code "60") (name "/K14{slash}COM") (class "Default")
      (node (ref "J18") (pin "2") (pinfunction "02_2") (pintype "passive"))
      (node (ref "K14") (pin "3") (pinfunction "11_3") (pintype "passive"))
    )
    (net (code "61") (name "/K14{slash}NC") (class "Default")
      (node (ref "J18") (pin "3") (pinfunction "03_3") (pintype "passive"))
      (node (ref "K14") (pin "4") (pinfunction "12_4") (pintype "passive"))
    )
    (net (code "62") (name "/K14{slash}NO") (class "Default")
      (node (ref "J18") (pin "1") (pinfunction "01_1") (pintype "passive"))
      (node (ref "K14") (pin "5") (pinfunction "14_5") (pintype "passive"))
    )
    (net (code "63") (name "/K15{slash}A2") (class "Default")
      (node (ref "K15") (pin "2") (pinfunction "A2_2") (pintype "passive"))
      (node (ref "U7") (pin "12") (pinfunction "7C_12") (pintype "bidirectional"))
    )
    (net (code "64") (name "/K15{slash}COM") (class "Default")
      (node (ref "J19") (pin "2") (pinfunction "02_2") (pintype "passive"))
      (node (ref "K15") (pin "3") (pinfunction "11_3") (pintype "passive"))
    )
    (net (code "65") (name "/K15{slash}NC") (class "Default")
      (node (ref "J19") (pin "3") (pinfunction "03_3") (pintype "passive"))
      (node (ref "K15") (pin "4") (pinfunction "12_4") (pintype "passive"))
    )
    (net (code "66") (name "/K15{slash}NO") (class "Default")
      (node (ref "J19") (pin "1") (pinfunction "01_1") (pintype "passive"))
      (node (ref "K15") (pin "5") (pinfunction "14_5") (pintype "passive"))
    )
    (net (code "67") (name "/K16{slash}A2") (class "Default")
      (node (ref "K16") (pin "2") (pinfunction "A2_2") (pintype "passive"))
      (node (ref "U7") (pin "11") (pinfunction "8C_11") (pintype "bidirectional"))
    )
    (net (code "68") (name "/K16{slash}COM") (class "Default")
      (node (ref "J20") (pin "2") (pinfunction "02_2") (pintype "passive"))
      (node (ref "K16") (pin "3") (pinfunction "11_3") (pintype "passive"))
    )
    (net (code "69") (name "/K16{slash}NC") (class "Default")
      (node (ref "J20") (pin "3") (pinfunction "03_3") (pintype "passive"))
      (node (ref "K16") (pin "4") (pinfunction "12_4") (pintype "passive"))
    )
    (net (code "70") (name "/K16{slash}NO") (class "Default")
      (node (ref "J20") (pin "1") (pinfunction "01_1") (pintype "passive"))
      (node (ref "K16") (pin "5") (pinfunction "14_5") (pintype "passive"))
    )
    (net (code "71") (name "/MODE") (class "Default")
      (node (ref "R24") (pin "2") (pinfunction "2_2") (pintype "passive"))
      (node (ref "S2") (pin "1") (pinfunction "1_1") (pintype "bidirectional"))
      (node (ref "S2") (pin "2") (pinfunction "2_2") (pintype "bidirectional"))
      (node (ref "U3") (pin "14") (pinfunction "GPIO12/ADC2CH5_14") (pintype "bidirectional"))
    )
    (net (code "72") (name "/O1") (class "Default")
      (node (ref "R8") (pin "1") (pinfunction "1_1") (pintype "passive"))
      (node (ref "U4") (pin "15") (pinfunction "Q0_15") (pintype "bidirectional"))
      (node (ref "U6") (pin "1") (pinfunction "1B_1") (pintype "bidirectional"))
    )
    (net (code "73") (name "/O2") (class "Default")
      (node (ref "R9") (pin "1") (pinfunction "1_1") (pintype "passive"))
      (node (ref "U4") (pin "1") (pinfunction "Q1_1") (pintype "bidirectional"))
      (node (ref "U6") (pin "2") (pinfunction "2B_2") (pintype "bidirectional"))
    )
    (net (code "74") (name "/O3") (class "Default")
      (node (ref "R10") (pin "1") (pinfunction "1_1") (pintype "passive"))
      (node (ref "U4") (pin "2") (pinfunction "Q2_2") (pintype "bidirectional"))
      (node (ref "U6") (pin "3") (pinfunction "3B_3") (pintype "bidirectional"))
    )
    (net (code "75") (name "/O4") (class "Default")
      (node (ref "R11") (pin "1") (pinfunction "1_1") (pintype "passive"))
      (node (ref "U4") (pin "3") (pinfunction "Q3_3") (pintype "bidirectional"))
      (node (ref "U6") (pin "4") (pinfunction "4B_4") (pintype "bidirectional"))
    )
    (net (code "76") (name "/O5") (class "Default")
      (node (ref "R12") (pin "1") (pinfunction "1_1") (pintype "passive"))
      (node (ref "U4") (pin "4") (pinfunction "Q4_4") (pintype "bidirectional"))
      (node (ref "U6") (pin "5") (pinfunction "5B_5") (pintype "bidirectional"))
    )
    (net (code "77") (name "/O6") (class "Default")
      (node (ref "R13") (pin "1") (pinfunction "1_1") (pintype "passive"))
      (node (ref "U4") (pin "5") (pinfunction "Q5_5") (pintype "bidirectional"))
      (node (ref "U6") (pin "6") (pinfunction "6B_6") (pintype "bidirectional"))
    )
    (net (code "78") (name "/O7") (class "Default")
      (node (ref "R14") (pin "1") (pinfunction "1_1") (pintype "passive"))
      (node (ref "U4") (pin "6") (pinfunction "Q6_6") (pintype "bidirectional"))
      (node (ref "U6") (pin "7") (pinfunction "7B_7") (pintype "bidirectional"))
    )
    (net (code "79") (name "/O8") (class "Default")
      (node (ref "R15") (pin "1") (pinfunction "1_1") (pintype "passive"))
      (node (ref "U4") (pin "7") (pinfunction "Q7_7") (pintype "bidirectional"))
      (node (ref "U6") (pin "8") (pinfunction "8B_8") (pintype "bidirectional"))
    )
    (net (code "80") (name "/O9") (class "Default")
      (node (ref "R16") (pin "1") (pinfunction "1_1") (pintype "passive"))
      (node (ref "U5") (pin "15") (pinfunction "Q0_15") (pintype "bidirectional"))
      (node (ref "U7") (pin "1") (pinfunction "1B_1") (pintype "bidirectional"))
    )
    (net (code "81") (name "/O10") (class "Default")
      (node (ref "R17") (pin "1") (pinfunction "1_1") (pintype "passive"))
      (node (ref "U5") (pin "1") (pinfunction "Q1_1") (pintype "bidirectional"))
      (node (ref "U7") (pin "2") (pinfunction "2B_2") (pintype "bidirectional"))
    )
    (net (code "82") (name "/O11") (class "Default")
      (node (ref "R18") (pin "1") (pinfunction "1_1") (pintype "passive"))
      (node (ref "U5") (pin "2") (pinfunction "Q2_2") (pintype "bidirectional"))
      (node (ref "U7") (pin "3") (pinfunction "3B_3") (pintype "bidirectional"))
    )
    (net (code "83") (name "/O12") (class "Default")
      (node (ref "R19") (pin "1") (pinfunction "1_1") (pintype "passive"))
      (node (ref "U5") (pin "3") (pinfunction "Q3_3") (pintype "bidirectional"))
      (node (ref "U7") (pin "4") (pinfunction "4B_4") (pintype "bidirectional"))
    )
    (net (code "84") (name "/O13") (class "Default")
      (node (ref "R20") (pin "1") (pinfunction "1_1") (pintype "passive"))
      (node (ref "U5") (pin "4") (pinfunction "Q4_4") (pintype "bidirectional"))
      (node (ref "U7") (pin "5") (pinfunction "5B_5") (pintype "bidirectional"))
    )
    (net (code "85") (name "/O14") (class "Default")
      (node (ref "R21") (pin "1") (pinfunction "1_1") (pintype "passive"))
      (node (ref "U5") (pin "5") (pinfunction "Q5_5") (pintype "bidirectional"))
      (node (ref "U7") (pin "6") (pinfunction "6B_6") (pintype "bidirectional"))
    )
    (net (code "86") (name "/O15") (class "Default")
      (node (ref "R22") (pin "1") (pinfunction "1_1") (pintype "passive"))
      (node (ref "U5") (pin "6") (pinfunction "Q6_6") (pintype "bidirectional"))
      (node (ref "U7") (pin "7") (pinfunction "7B_7") (pintype "bidirectional"))
    )
    (net (code "87") (name "/O16") (class "Default")
      (node (ref "R23") (pin "1") (pinfunction "1_1") (pintype "passive"))
      (node (ref "U5") (pin "7") (pinfunction "Q7_7") (pintype "bidirectional"))
      (node (ref "U7") (pin "8") (pinfunction "8B_8") (pintype "bidirectional"))
    )
    (net (code "88") (name "/Q7S") (class "Default")
      (node (ref "U4") (pin "9") (pinfunction "Q7S_9") (pintype "bidirectional"))
      (node (ref "U5") (pin "14") (pinfunction "DS_14") (pintype "bidirectional"))
    )
    (net (code "89") (name "/RXD0") (class "Default")
      (node (ref "U1") (pin "26") (pinfunction "TXD_26") (pintype "bidirectional"))
      (node (ref "U3") (pin "34") (pinfunction "GPIO03/RXD0_34") (pintype "bidirectional"))
    )
    (net (code "90") (name "/SHCP") (class "Default")
      (node (ref "U3") (pin "11") (pinfunction "GPIO26/ADC2CH9_11") (pintype "bidirectional"))
      (node (ref "U4") (pin "11") (pinfunction "SHCP_11") (pintype "bidirectional"))
      (node (ref "U5") (pin "11") (pinfunction "SHCP_11") (pintype "bidirectional"))
    )
    (net (code "91") (name "/STCP") (class "Default")
      (node (ref "U3") (pin "12") (pinfunction "GPIO27/ADC2CH7_12") (pintype "bidirectional"))
      (node (ref "U4") (pin "12") (pinfunction "STCP_12") (pintype "bidirectional"))
      (node (ref "U5") (pin "12") (pinfunction "STCP_12") (pintype "bidirectional"))
    )
    (net (code "92") (name "/TXD0") (class "Default")
      (node (ref "U1") (pin "25") (pinfunction "RXD_25") (pintype "bidirectional"))
      (node (ref "U3") (pin "35") (pinfunction "GPIO01/TXD0_35") (pintype "bidirectional"))
    )
    (net (code "93") (name "/~{MR}") (class "Default")
      (node (ref "U3") (pin "8") (pinfunction "GPIO32/ADC1CH4_8") (pintype "bidirectional"))
      (node (ref "U4") (pin "10") (pinfunction "~{MR}_10") (pintype "bidirectional"))
      (node (ref "U5") (pin "10") (pinfunction "~{MR}_10") (pintype "bidirectional"))
    )
    (net (code "94") (name "AC{slash}L") (class "Default")
      (node (ref "J2") (pin "2") (pinfunction "02_2") (pintype "passive"))
      (node (ref "PU1") (pin "1") (pinfunction "AC/L_1") (pintype "power_in"))
    )
    (net (code "95") (name "AC{slash}N") (class "Default")
      (node (ref "J2") (pin "1") (pinfunction "01_1") (pintype "passive"))
      (node (ref "PU1") (pin "2") (pinfunction "AC/N_2") (pintype "power_in"))
    )
    (net (code "96") (name "GND") (class "Default")
      (node (ref "C1") (pin "2") (pinfunction "-_2") (pintype "passive"))
      (node (ref "C10") (pin "2") (pinfunction "2_2") (pintype "passive"))
      (node (ref "C11") (pin "2") (pinfunction "2_2") (pintype "passive"))
      (node (ref "C2") (pin "1") (pinfunction "1_1") (pintype "passive"))
      (node (ref "C3") (pin "1") (pinfunction "1_1") (pintype "passive"))
      (node (ref "C4") (pin "2") (pinfunction "-_2") (pintype "passive"))
      (node (ref "C5") (pin "2") (pinfunction "-_2") (pintype "passive"))
      (node (ref "C6") (pin "2") (pinfunction "-_2") (pintype "passive"))
      (node (ref "C7") (pin "2") (pinfunction "2_2") (pintype "passive"))
      (node (ref "C8") (pin "2") (pinfunction "2_2") (pintype "passive"))
      (node (ref "C9") (pin "1") (pinfunction "1_1") (pintype "passive"))
      (node (ref "D1") (pin "2") (pinfunction "C_2") (pintype "passive"))
      (node (ref "D3") (pin "2") (pinfunction "C_2") (pintype "passive"))
      (node (ref "D4") (pin "2") (pinfunction "C_2") (pintype "passive"))
      (node (ref "J1") (pin "5") (pinfunction "GND_5") (pintype "power_in"))
      (node (ref "J1") (pin "6") (pinfunction "GND_6") (pintype "power_in"))
      (node (ref "J1") (pin "7") (pinfunction "GND_7") (pintype "power_in"))
      (node (ref "LED1") (pin "2") (pinfunction "C_2") (pintype "passive"))
      (node (ref "LED10") (pin "2") (pinfunction "C_2") (pintype "passive"))
      (node (ref "LED11") (pin "2") (pinfunction "C_2") (pintype "passive"))
      (node (ref "LED12") (pin "2") (pinfunction "C_2") (pintype "passive"))
      (node (ref "LED13") (pin "2") (pinfunction "C_2") (pintype "passive"))
      (node (ref "LED14") (pin "2") (pinfunction "C_2") (pintype "passive"))
      (node (ref "LED15") (pin "2") (pinfunction "C_2") (pintype "passive"))
      (node (ref "LED16") (pin "2") (pinfunction "C_2") (pintype "passive"))
      (node (ref "LED17") (pin "2") (pinfunction "C_2") (pintype "passive"))
      (node (ref "LED18") (pin "2") (pinfunction "C_2") (pintype "passive"))
      (node (ref "LED19") (pin "2") (pinfunction "C_2") (pintype "passive"))
      (node (ref "LED2") (pin "2") (pinfunction "C_2") (pintype "passive"))
      (node (ref "LED20") (pin "2") (pinfunction "C_2") (pintype "passive"))
      (node (ref "LED5") (pin "2") (pinfunction "C_2") (pintype "passive"))
      (node (ref "LED6") (pin "2") (pinfunction "C_2") (pintype "passive"))
      (node (ref "LED7") (pin "2") (pinfunction "C_2") (pintype "passive"))
      (node (ref "LED8") (pin "2") (pinfunction "C_2") (pintype "passive"))
      (node (ref "LED9") (pin "2") (pinfunction "C_2") (pintype "passive"))
      (node (ref "PU1") (pin "4") (pinfunction "GND_4") (pintype "power_in"))
      (node (ref "S1") (pin "3") (pinfunction "3_3") (pintype "bidirectional"))
      (node (ref "S1") (pin "4") (pinfunction "4_4") (pintype "bidirectional"))
      (node (ref "S2") (pin "3") (pinfunction "3_3") (pintype "bidirectional"))
      (node (ref "S2") (pin "4") (pinfunction "4_4") (pintype "bidirectional"))
      (node (ref "T3") (pin "2") (pinfunction "E_2") (pintype "passive"))
      (node (ref "U1") (pin "29") (pinfunction "GND_29") (pintype "power_in"))
      (node (ref "U1") (pin "3") (pinfunction "GND_3") (pintype "power_in"))
      (node (ref "U1") (pin "30") (pinfunction "GND_30") (pintype "power_in"))
      (node (ref "U1") (pin "31") (pinfunction "GND_31") (pintype "power_in"))
      (node (ref "U1") (pin "32") (pinfunction "GND_32") (pintype "power_in"))
      (node (ref "U1") (pin "33") (pinfunction "GND_33") (pintype "power_in"))
      (node (ref "U1") (pin "34") (pinfunction "GND_34") (pintype "power_in"))
      (node (ref "U1") (pin "35") (pinfunction "GND_35") (pintype "power_in"))
      (node (ref "U1") (pin "36") (pinfunction "GND_36") (pintype "power_in"))
      (node (ref "U1") (pin "37") (pinfunction "GND_37") (pintype "power_in"))
      (node (ref "U1") (pin "38") (pinfunction "GND_38") (pintype "power_in"))
      (node (ref "U3") (pin "1") (pinfunction "GND_1") (pintype "power_in"))
      (node (ref "U3") (pin "15") (pinfunction "GND_15") (pintype "power_in"))
      (node (ref "U3") (pin "23") (pinfunction "GPIO15/ADC2CH3_23") (pintype "bidirectional"))
      (node (ref "U3") (pin "38") (pinfunction "GND_38") (pintype "bidirectional"))
      (node (ref "U3") (pin "39") (pinfunction "GND_39") (pintype "power_in"))
      (node (ref "U3") (pin "40") (pinfunction "GND_40") (pintype "power_in"))
      (node (ref "U3") (pin "41") (pinfunction "GND_41") (pintype "power_in"))
      (node (ref "U3") (pin "42") (pinfunction "GND_42") (pintype "power_in"))
      (node (ref "U3") (pin "43") (pinfunction "GND_43") (pintype "power_in"))
      (node (ref "U3") (pin "44") (pinfunction "GND_44") (pintype "power_in"))
      (node (ref "U3") (pin "45") (pinfunction "GND_45") (pintype "power_in"))
      (node (ref "U3") (pin "46") (pinfunction "GND_46") (pintype "power_in"))
      (node (ref "U3") (pin "47") (pinfunction "GND_47") (pintype "power_in"))
      (node (ref "U3") (pin "48") (pinfunction "GND_48") (pintype "power_in"))
      (node (ref "U4") (pin "13") (pinfunction "~{OE}_13") (pintype "bidirectional"))
      (node (ref "U4") (pin "8") (pinfunction "GND_8") (pintype "power_in"))
      (node (ref "U5") (pin "13") (pinfunction "~{OE}_13") (pintype "bidirectional"))
      (node (ref "U5") (pin "8") (pinfunction "GND_8") (pintype "power_in"))
      (node (ref "U6") (pin "9") (pinfunction "GND_9") (pintype "power_in"))
      (node (ref "U7") (pin "9") (pinfunction "GND_9") (pintype "power_in"))
      (node (ref "U8") (pin "2") (pinfunction "GND_2") (pintype "power_in"))
    )
    (net (code "97") (name "Net-(D8-A)") (class "Default")
      (node (ref "D8") (pin "1") (pinfunction "A_1") (pintype "passive"))
      (node (ref "T3") (pin "3") (pinfunction "C_3") (pintype "passive"))
      (node (ref "U2") (pin "2") (pinfunction "-_2") (pintype "bidirectional"))
    )
    (net (code "98") (name "Net-(LED1-A)") (class "Default")
      (node (ref "LED1") (pin "1") (pinfunction "A_1") (pintype "passive"))
      (node (ref "R4") (pin "2") (pinfunction "2_2") (pintype "passive"))
    )
    (net (code "99") (name "Net-(LED2-A)") (class "Default")
      (node (ref "LED2") (pin "1") (pinfunction "A_1") (pintype "passive"))
      (node (ref "R5") (pin "2") (pinfunction "2_2") (pintype "passive"))
    )
    (net (code "100") (name "Net-(LED5-A)") (class "Default")
      (node (ref "LED5") (pin "1") (pinfunction "A_1") (pintype "passive"))
      (node (ref "R8") (pin "2") (pinfunction "2_2") (pintype "passive"))
    )
    (net (code "101") (name "Net-(LED6-A)") (class "Default")
      (node (ref "LED6") (pin "1") (pinfunction "A_1") (pintype "passive"))
      (node (ref "R9") (pin "2") (pinfunction "2_2") (pintype "passive"))
    )
    (net (code "102") (name "Net-(LED7-A)") (class "Default")
      (node (ref "LED7") (pin "1") (pinfunction "A_1") (pintype "passive"))
      (node (ref "R10") (pin "2") (pinfunction "2_2") (pintype "passive"))
    )
    (net (code "103") (name "Net-(LED8-A)") (class "Default")
      (node (ref "LED8") (pin "1") (pinfunction "A_1") (pintype "passive"))
      (node (ref "R11") (pin "2") (pinfunction "2_2") (pintype "passive"))
    )
    (net (code "104") (name "Net-(LED9-A)") (class "Default")
      (node (ref "LED9") (pin "1") (pinfunction "A_1") (pintype "passive"))
      (node (ref "R12") (pin "2") (pinfunction "2_2") (pintype "passive"))
    )
    (net (code "105") (name "Net-(LED10-A)") (class "Default")
      (node (ref "LED10") (pin "1") (pinfunction "A_1") (pintype "passive"))
      (node (ref "R13") (pin "2") (pinfunction "2_2") (pintype "passive"))
    )
    (net (code "106") (name "Net-(LED11-A)") (class "Default")
      (node (ref "LED11") (pin "1") (pinfunction "A_1") (pintype "passive"))
      (node (ref "R14") (pin "2") (pinfunction "2_2") (pintype "passive"))
    )
    (net (code "107") (name "Net-(LED12-A)") (class "Default")
      (node (ref "LED12") (pin "1") (pinfunction "A_1") (pintype "passive"))
      (node (ref "R15") (pin "2") (pinfunction "2_2") (pintype "passive"))
    )
    (net (code "108") (name "Net-(LED13-A)") (class "Default")
      (node (ref "LED13") (pin "1") (pinfunction "A_1") (pintype "passive"))
      (node (ref "R16") (pin "2") (pinfunction "2_2") (pintype "passive"))
    )
    (net (code "109") (name "Net-(LED14-A)") (class "Default")
      (node (ref "LED14") (pin "1") (pinfunction "A_1") (pintype "passive"))
      (node (ref "R17") (pin "2") (pinfunction "2_2") (pintype "passive"))
    )
    (net (code "110") (name "Net-(LED15-A)") (class "Default")
      (node (ref "LED15") (pin "1") (pinfunction "A_1") (pintype "passive"))
      (node (ref "R18") (pin "2") (pinfunction "2_2") (pintype "passive"))
    )
    (net (code "111") (name "Net-(LED16-A)") (class "Default")
      (node (ref "LED16") (pin "1") (pinfunction "A_1") (pintype "passive"))
      (node (ref "R19") (pin "2") (pinfunction "2_2") (pintype "passive"))
    )
    (net (code "112") (name "Net-(LED17-A)") (class "Default")
      (node (ref "LED17") (pin "1") (pinfunction "A_1") (pintype "passive"))
      (node (ref "R20") (pin "2") (pinfunction "2_2") (pintype "passive"))
    )
    (net (code "113") (name "Net-(LED18-A)") (class "Default")
      (node (ref "LED18") (pin "1") (pinfunction "A_1") (pintype "passive"))
      (node (ref "R21") (pin "2") (pinfunction "2_2") (pintype "passive"))
    )
    (net (code "114") (name "Net-(LED19-A)") (class "Default")
      (node (ref "LED19") (pin "1") (pinfunction "A_1") (pintype "passive"))
      (node (ref "R22") (pin "2") (pinfunction "2_2") (pintype "passive"))
    )
    (net (code "115") (name "Net-(LED20-A)") (class "Default")
      (node (ref "LED20") (pin "1") (pinfunction "A_1") (pintype "passive"))
      (node (ref "R23") (pin "2") (pinfunction "2_2") (pintype "passive"))
    )
    (net (code "116") (name "Net-(T1-B)") (class "Default")
      (node (ref "R1") (pin "2") (pinfunction "2_2") (pintype "passive"))
      (node (ref "T1") (pin "1") (pinfunction "B_1") (pintype "passive"))
    )
    (net (code "117") (name "Net-(T1-E)") (class "Default")
      (node (ref "R2") (pin "1") (pinfunction "1_1") (pintype "passive"))
      (node (ref "T1") (pin "2") (pinfunction "E_2") (pintype "passive"))
      (node (ref "U1") (pin "24") (pinfunction "RTS_24") (pintype "bidirectional"))
    )
    (net (code "118") (name "Net-(T2-B)") (class "Default")
      (node (ref "R2") (pin "2") (pinfunction "2_2") (pintype "passive"))
      (node (ref "T2") (pin "1") (pinfunction "B_1") (pintype "passive"))
    )
    (net (code "119") (name "Net-(T2-E)") (class "Default")
      (node (ref "R1") (pin "1") (pinfunction "1_1") (pintype "passive"))
      (node (ref "T2") (pin "2") (pinfunction "E_2") (pintype "passive"))
      (node (ref "U1") (pin "28") (pinfunction "DTR_28") (pintype "bidirectional"))
    )
    (net (code "120") (name "Net-(T3-B)") (class "Default")
      (node (ref "R25") (pin "2") (pinfunction "2_2") (pintype "passive"))
      (node (ref "T3") (pin "1") (pinfunction "B_1") (pintype "passive"))
    )
    (net (code "121") (name "Net-(U1-VDD)") (class "Default")
      (node (ref "C9") (pin "2") (pinfunction "2_2") (pintype "passive"))
      (node (ref "U1") (pin "6") (pinfunction "VDD_6") (pintype "power_in"))
    )
    (net (code "122") (name "Net-(U8-EN)") (class "Default")
      (node (ref "R6") (pin "2") (pinfunction "2_2") (pintype "passive"))
      (node (ref "U8") (pin "3") (pinfunction "EN_3") (pintype "bidirectional"))
    )
    (net (code "123") (name "VBUS") (class "Default")
      (node (ref "C2") (pin "2") (pinfunction "2_2") (pintype "passive"))
      (node (ref "C3") (pin "2") (pinfunction "2_2") (pintype "passive"))
      (node (ref "D1") (pin "1") (pinfunction "A_1") (pintype "passive"))
      (node (ref "D5") (pin "1") (pinfunction "A_1") (pintype "passive"))
      (node (ref "J1") (pin "1") (pinfunction "VBUS_1") (pintype "power_in"))
      (node (ref "U1") (pin "7") (pinfunction "REGIN_7") (pintype "bidirectional"))
      (node (ref "U1") (pin "8") (pinfunction "VBUS_8") (pintype "bidirectional"))
    )
    (net (code "124") (name "VCC3") (class "Default")
      (node (ref "C10") (pin "1") (pinfunction "1_1") (pintype "passive"))
      (node (ref "C11") (pin "1") (pinfunction "1_1") (pintype "passive"))
      (node (ref "C5") (pin "1") (pinfunction "+_1") (pintype "passive"))
      (node (ref "C6") (pin "1") (pinfunction "+_1") (pintype "passive"))
      (node (ref "C7") (pin "1") (pinfunction "1_1") (pintype "passive"))
      (node (ref "D8") (pin "2") (pinfunction "C_2") (pintype "passive"))
      (node (ref "R24") (pin "1") (pinfunction "1_1") (pintype "passive"))
      (node (ref "R3") (pin "1") (pinfunction "1_1") (pintype "passive"))
      (node (ref "R5") (pin "1") (pinfunction "1_1") (pintype "passive"))
      (node (ref "U2") (pin "1") (pinfunction "+_1") (pintype "bidirectional"))
      (node (ref "U3") (pin "2") (pinfunction "VCC_2") (pintype "power_in"))
      (node (ref "U4") (pin "16") (pinfunction "VCC_16") (pintype "power_in"))
      (node (ref "U5") (pin "16") (pinfunction "VCC_16") (pintype "power_in"))
      (node (ref "U8") (pin "5") (pinfunction "VOUT_5") (pintype "power_in"))
    )
    (net (code "125") (name "VCC5") (class "Default")
      (node (ref "C1") (pin "1") (pinfunction "+_1") (pintype "passive"))
      (node (ref "D2") (pin "1") (pinfunction "A_1") (pintype "passive"))
      (node (ref "K1") (pin "1") (pinfunction "A1_1") (pintype "passive"))
      (node (ref "K10") (pin "1") (pinfunction "A1_1") (pintype "passive"))
      (node (ref "K11") (pin "1") (pinfunction "A1_1") (pintype "passive"))
      (node (ref "K12") (pin "1") (pinfunction "A1_1") (pintype "passive"))
      (node (ref "K13") (pin "1") (pinfunction "A1_1") (pintype "passive"))
      (node (ref "K14") (pin "1") (pinfunction "A1_1") (pintype "passive"))
      (node (ref "K15") (pin "1") (pinfunction "A1_1") (pintype "passive"))
      (node (ref "K16") (pin "1") (pinfunction "A1_1") (pintype "passive"))
      (node (ref "K2") (pin "1") (pinfunction "A1_1") (pintype "passive"))
      (node (ref "K3") (pin "1") (pinfunction "A1_1") (pintype "passive"))
      (node (ref "K4") (pin "1") (pinfunction "A1_1") (pintype "passive"))
      (node (ref "K5") (pin "1") (pinfunction "A1_1") (pintype "passive"))
      (node (ref "K6") (pin "1") (pinfunction "A1_1") (pintype "passive"))
      (node (ref "K7") (pin "1") (pinfunction "A1_1") (pintype "passive"))
      (node (ref "K8") (pin "1") (pinfunction "A1_1") (pintype "passive"))
      (node (ref "K9") (pin "1") (pinfunction "A1_1") (pintype "passive"))
      (node (ref "PU1") (pin "3") (pinfunction "VCC_3") (pintype "power_in"))
      (node (ref "R4") (pin "1") (pinfunction "1_1") (pintype "passive"))
      (node (ref "U6") (pin "10") (pinfunction "COM_10") (pintype "bidirectional"))
      (node (ref "U7") (pin "10") (pinfunction "COM_10") (pintype "bidirectional"))
    )
    (net (code "126") (name "VIN") (class "Default")
      (node (ref "C4") (pin "1") (pinfunction "+_1") (pintype "passive"))
      (node (ref "D2") (pin "2") (pinfunction "C_2") (pintype "passive"))
      (node (ref "D5") (pin "2") (pinfunction "C_2") (pintype "passive"))
      (node (ref "R6") (pin "1") (pinfunction "1_1") (pintype "passive"))
      (node (ref "U8") (pin "1") (pinfunction "VIN_1") (pintype "power_in"))
    )
    (net (code "127") (name "unconnected-(J1-ID-Pad4)") (class "Default")
      (node (ref "J1") (pin "4") (pinfunction "ID_4") (pintype "passive"))
    )
    (net (code "128") (name "unconnected-(U1-CTS-Pad23)") (class "Default")
      (node (ref "U1") (pin "23") (pinfunction "CTS_23") (pintype "bidirectional"))
    )
    (net (code "129") (name "unconnected-(U1-DCD-Pad1)") (class "Default")
      (node (ref "U1") (pin "1") (pinfunction "DCD_1") (pintype "bidirectional"))
    )
    (net (code "130") (name "unconnected-(U1-DSR-Pad27)") (class "Default")
      (node (ref "U1") (pin "27") (pinfunction "DSR_27") (pintype "bidirectional"))
    )
    (net (code "131") (name "unconnected-(U1-RI-Pad2)") (class "Default")
      (node (ref "U1") (pin "2") (pinfunction "RI_2") (pintype "bidirectional"))
    )
    (net (code "132") (name "unconnected-(U1-SUSPEND-Pad12)") (class "Default")
      (node (ref "U1") (pin "12") (pinfunction "SUSPEND_12") (pintype "bidirectional"))
    )
    (net (code "133") (name "unconnected-(U1-~{RST}-Pad9)") (class "Default")
      (node (ref "U1") (pin "9") (pinfunction "~{RST}_9") (pintype "bidirectional"))
    )
    (net (code "134") (name "unconnected-(U1-~{SUSPEND}-Pad11)") (class "Default")
      (node (ref "U1") (pin "11") (pinfunction "~{SUSPEND}_11") (pintype "bidirectional"))
    )
    (net (code "135") (name "unconnected-(U3-GIO19{slash}MISO-Pad31)") (class "Default")
      (node (ref "U3") (pin "31") (pinfunction "GIO19/MISO_31") (pintype "bidirectional"))
    )
    (net (code "136") (name "unconnected-(U3-GPIO02{slash}ADC2CH2-Pad24)") (class "Default")
      (node (ref "U3") (pin "24") (pinfunction "GPIO02/ADC2CH2_24") (pintype "bidirectional"))
    )
    (net (code "137") (name "unconnected-(U3-GPIO05{slash}CS0-Pad29)") (class "Default")
      (node (ref "U3") (pin "29") (pinfunction "GPIO05/CS0_29") (pintype "bidirectional"))
    )
    (net (code "138") (name "unconnected-(U3-GPIO06{slash}CLK-Pad20)") (class "Default")
      (node (ref "U3") (pin "20") (pinfunction "GPIO06/CLK_20") (pintype "bidirectional"))
    )
    (net (code "139") (name "unconnected-(U3-GPIO07{slash}SD0-Pad21)") (class "Default")
      (node (ref "U3") (pin "21") (pinfunction "GPIO07/SD0_21") (pintype "bidirectional"))
    )
    (net (code "140") (name "unconnected-(U3-GPIO08{slash}SD1-Pad22)") (class "Default")
      (node (ref "U3") (pin "22") (pinfunction "GPIO08/SD1_22") (pintype "bidirectional"))
    )
    (net (code "141") (name "unconnected-(U3-GPIO09{slash}SD2-Pad17)") (class "Default")
      (node (ref "U3") (pin "17") (pinfunction "GPIO09/SD2_17") (pintype "bidirectional"))
    )
    (net (code "142") (name "unconnected-(U3-GPIO10{slash}SD3-Pad18)") (class "Default")
      (node (ref "U3") (pin "18") (pinfunction "GPIO10/SD3_18") (pintype "bidirectional"))
    )
    (net (code "143") (name "unconnected-(U3-GPIO11{slash}CMD-Pad19)") (class "Default")
      (node (ref "U3") (pin "19") (pinfunction "GPIO11/CMD_19") (pintype "bidirectional"))
    )
    (net (code "144") (name "unconnected-(U3-GPIO13{slash}ADC2CH4-Pad16)") (class "Default")
      (node (ref "U3") (pin "16") (pinfunction "GPIO13/ADC2CH4_16") (pintype "bidirectional"))
    )
    (net (code "145") (name "unconnected-(U3-GPIO16{slash}RXD1-Pad27)") (class "Default")
      (node (ref "U3") (pin "27") (pinfunction "GPIO16/RXD1_27") (pintype "bidirectional"))
    )
    (net (code "146") (name "unconnected-(U3-GPIO17{slash}TXD1-Pad28)") (class "Default")
      (node (ref "U3") (pin "28") (pinfunction "GPIO17/TXD1_28") (pintype "bidirectional"))
    )
    (net (code "147") (name "unconnected-(U3-GPIO18{slash}CLK-Pad30)") (class "Default")
      (node (ref "U3") (pin "30") (pinfunction "GPIO18/CLK_30") (pintype "bidirectional"))
    )
    (net (code "148") (name "unconnected-(U3-GPIO21{slash}SDA-Pad33)") (class "Default")
      (node (ref "U3") (pin "33") (pinfunction "GPIO21/SDA_33") (pintype "bidirectional"))
    )
    (net (code "149") (name "unconnected-(U3-GPIO22{slash}SCL-Pad36)") (class "Default")
      (node (ref "U3") (pin "36") (pinfunction "GPIO22/SCL_36") (pintype "bidirectional"))
    )
    (net (code "150") (name "unconnected-(U3-GPIO23{slash}MOSI-Pad37)") (class "Default")
      (node (ref "U3") (pin "37") (pinfunction "GPIO23/MOSI_37") (pintype "bidirectional"))
    )
    (net (code "151") (name "unconnected-(U3-GPIO33{slash}ADC1CH5-Pad9)") (class "Default")
      (node (ref "U3") (pin "9") (pinfunction "GPIO33/ADC1CH5_9") (pintype "bidirectional"))
    )
    (net (code "152") (name "unconnected-(U3-GPIO34{slash}ADC1CH6-Pad6)") (class "Default")
      (node (ref "U3") (pin "6") (pinfunction "GPIO34/ADC1CH6_6") (pintype "bidirectional"))
    )
    (net (code "153") (name "unconnected-(U3-GPIO35{slash}ADC1CH7-Pad7)") (class "Default")
      (node (ref "U3") (pin "7") (pinfunction "GPIO35/ADC1CH7_7") (pintype "bidirectional"))
    )
    (net (code "154") (name "unconnected-(U3-GPIO36{slash}ADC1CH0{slash}SENSVP-Pad4)") (class "Default")
      (node (ref "U3") (pin "4") (pinfunction "GPIO36/ADC1CH0/SENSVP_4") (pintype "bidirectional"))
    )
    (net (code "155") (name "unconnected-(U3-GPIO39{slash}ADC1CH3{slash}SENSVN-Pad5)") (class "Default")
      (node (ref "U3") (pin "5") (pinfunction "GPIO39/ADC1CH3/SENSVN_5") (pintype "bidirectional"))
    )
    (net (code "156") (name "unconnected-(U5-Q7S-Pad9)") (class "Default")
      (node (ref "U5") (pin "9") (pinfunction "Q7S_9") (pintype "bidirectional"))
    )
  )
)
